# charge_controller.net
KiCad netlist of a schematic drawn in EAGLE
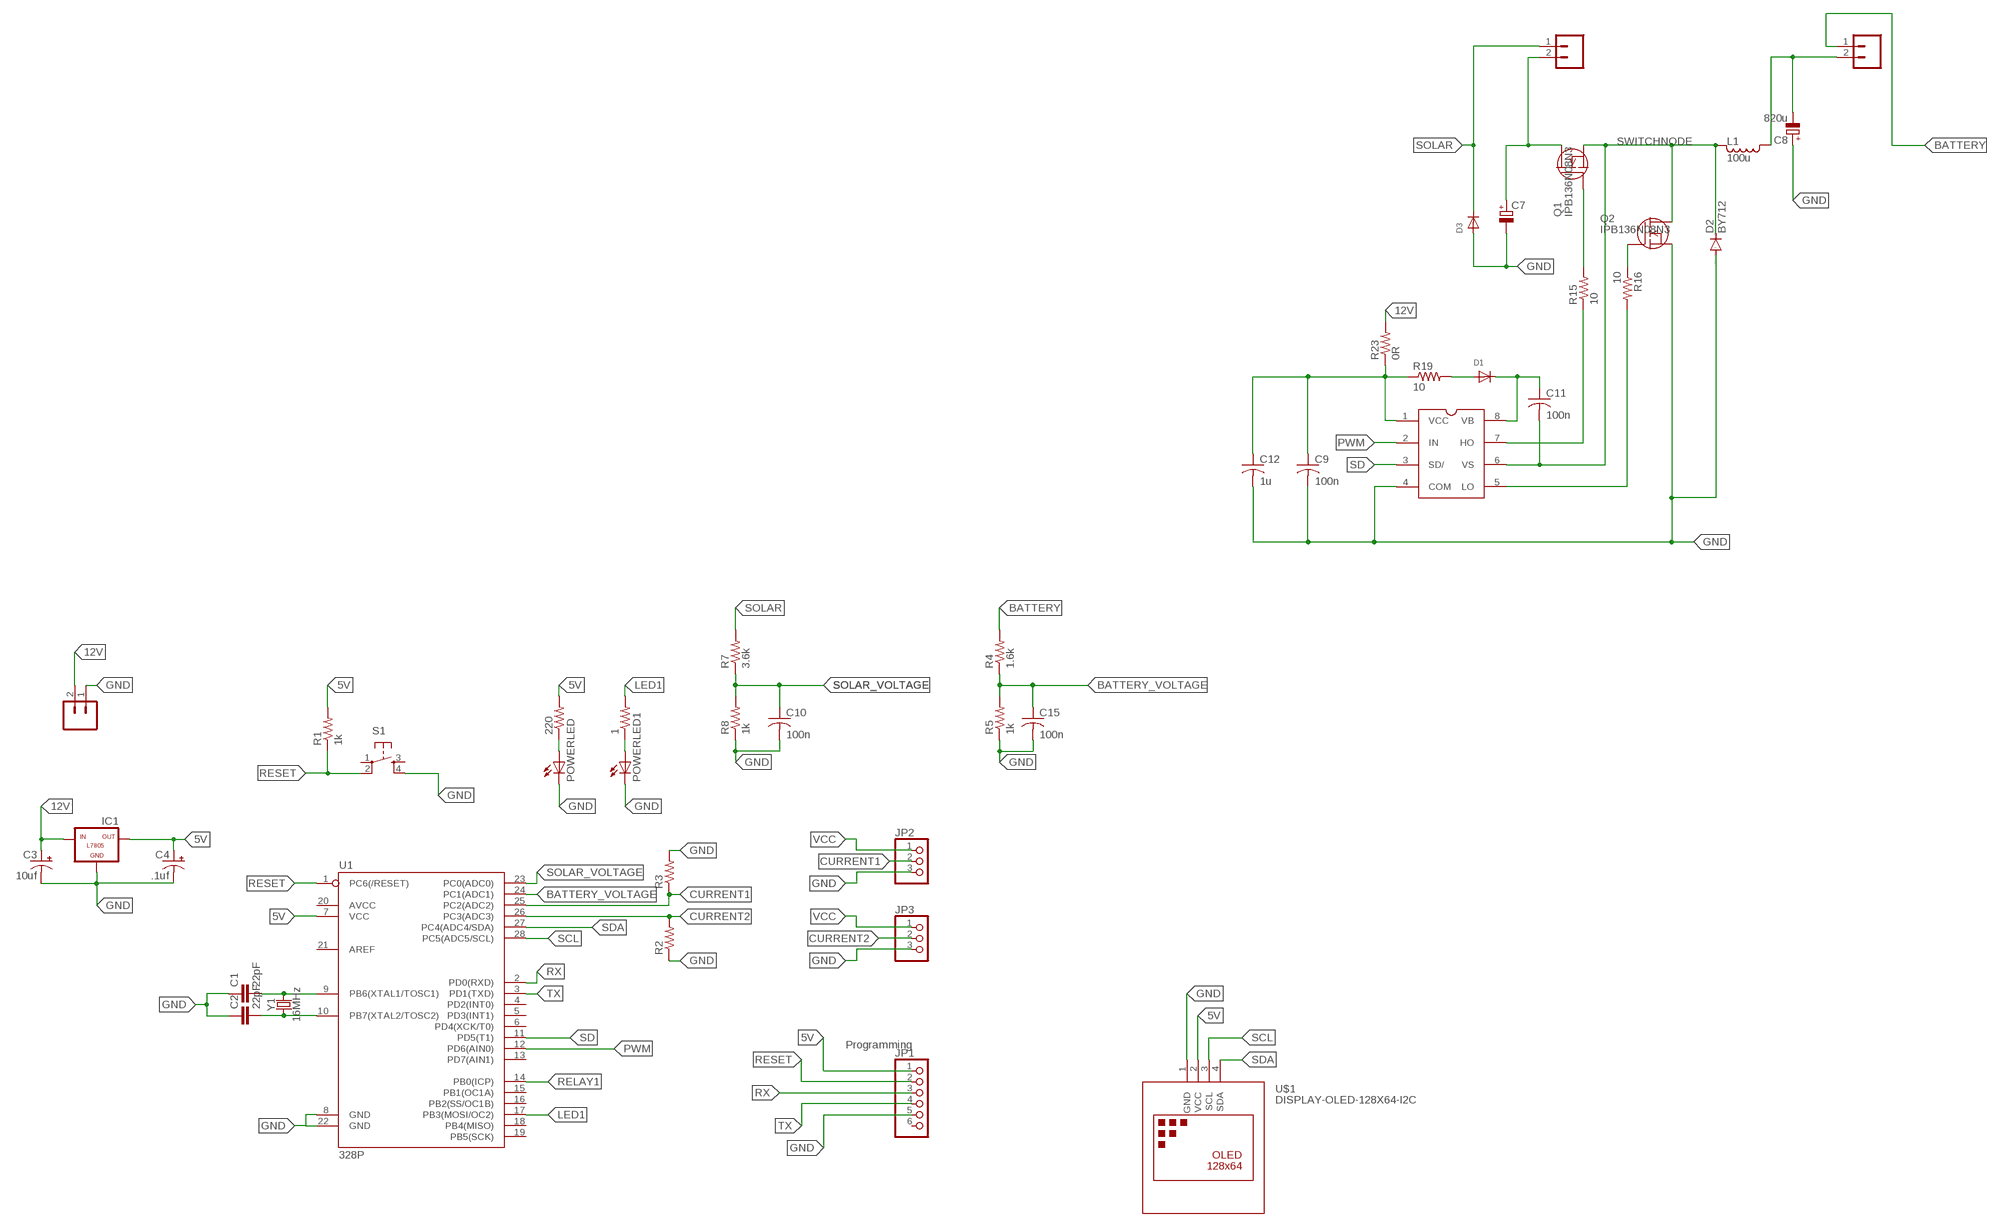
[diagram p0: schematic, sheet 1]

(export (version "E")
  (design (tool "Eeschema 10.0.6"))
  (components
    (comp (ref "1")
      (value "R-US_0204/5")
      (footprint "eagle-import:0204_5")
      (libsource (lib "eagle-import") (part "R-US_0204/5"))
    )
    (comp (ref "220")
      (value "R-US_0204/5")
      (footprint "eagle-import:0204_5")
      (libsource (lib "eagle-import") (part "R-US_0204/5"))
    )
    (comp (ref "BATTERY-OUT")
      (value "CONN_023.5MM_LOCK")
      (footprint "eagle-import:SCREWTERMINAL-3.5MM-2_LOCK")
      (libsource (lib "eagle-import") (part "CONN_023.5MM_LOCK"))
    )
    (comp (ref "C1")
      (value "22pF")
      (footprint "eagle-import:CAP-PTH-2.54")
      (libsource (lib "eagle-import") (part "22PF-PTH-2.54MM-200V-5%"))
    )
    (comp (ref "C2")
      (value "22pF")
      (footprint "eagle-import:CAP-PTH-2.54")
      (libsource (lib "eagle-import") (part "22PF-PTH-2.54MM-200V-5%"))
    )
    (comp (ref "C3")
      (value "10uf")
      (footprint "eagle-import:E5-5")
      (libsource (lib "eagle-import") (part "CPOL-USE5-5"))
    )
    (comp (ref "C4")
      (value ".1uf")
      (footprint "eagle-import:E5-5")
      (libsource (lib "eagle-import") (part "CPOL-USE5-5"))
    )
    (comp (ref "C7")
      (value "680u")
      (footprint "eagle-import:10MM")
      (libsource (lib "eagle-import") (part "C_POLARIZED10MM"))
    )
    (comp (ref "C8")
      (value "820u")
      (footprint "eagle-import:10MM")
      (libsource (lib "eagle-import") (part "C_POLARIZED10MM"))
    )
    (comp (ref "C9")
      (value "100n")
      (footprint "eagle-import:C050-025X075")
      (libsource (lib "eagle-import") (part "C-US050-025X075"))
    )
    (comp (ref "C10")
      (value "100n")
      (footprint "eagle-import:C050-025X075")
      (libsource (lib "eagle-import") (part "C-US050-025X075"))
    )
    (comp (ref "C11")
      (value "100n")
      (footprint "eagle-import:C050-055X075")
      (libsource (lib "eagle-import") (part "C-US050-055X075"))
    )
    (comp (ref "C12")
      (value "1u")
      (footprint "eagle-import:C050-025X075")
      (libsource (lib "eagle-import") (part "C-US050-025X075"))
    )
    (comp (ref "C15")
      (value "100n")
      (footprint "eagle-import:C050-025X075")
      (libsource (lib "eagle-import") (part "C-US050-025X075"))
    )
    (comp (ref "D1")
      (value "DIODEDO-1N4148")
      (footprint "eagle-import:DO-1N4148")
      (libsource (lib "eagle-import") (part "DIODEDO-1N4148"))
    )
    (comp (ref "D2")
      (value "BY712")
      (footprint "eagle-import:SOD61E")
      (libsource (lib "eagle-import") (part "BY712"))
    )
    (comp (ref "D3")
      (value "DIODEDO-1N4148")
      (footprint "eagle-import:DO-1N4148")
      (libsource (lib "eagle-import") (part "DIODEDO-1N4148"))
    )
    (comp (ref "IC1")
      (value "L7805")
      (footprint "eagle-import:78XXL")
      (libsource (lib "eagle-import") (part "L7805"))
    )
    (comp (ref "J1")
      (value "CONN_023.5MM_LOCK")
      (footprint "eagle-import:SCREWTERMINAL-3.5MM-2_LOCK")
      (libsource (lib "eagle-import") (part "CONN_023.5MM_LOCK"))
    )
    (comp (ref "JP1")
      (value "PINHD-1X6")
      (footprint "eagle-import:1X06")
      (libsource (lib "eagle-import") (part "PINHD-1X6"))
    )
    (comp (ref "JP2")
      (value "PINHD-1X3")
      (footprint "eagle-import:1X03")
      (libsource (lib "eagle-import") (part "PINHD-1X3"))
    )
    (comp (ref "JP3")
      (value "PINHD-1X3")
      (footprint "eagle-import:1X03")
      (libsource (lib "eagle-import") (part "PINHD-1X3"))
    )
    (comp (ref "L1")
      (value "100u")
      (footprint "eagle-import:MSS1583")
      (libsource (lib "eagle-import") (part "INDUCTORMSS1583"))
    )
    (comp (ref "POWERLED")
      (value "LED5MM")
      (footprint "eagle-import:LED5MM")
      (libsource (lib "eagle-import") (part "LED5MM"))
    )
    (comp (ref "POWERLED1")
      (value "LED5MM")
      (footprint "eagle-import:LED5MM")
      (libsource (lib "eagle-import") (part "LED5MM"))
    )
    (comp (ref "Q1")
      (value "IPB136N08N3")
      (footprint "eagle-import:TO220")
      (libsource (lib "eagle-import") (part "IRF840"))
    )
    (comp (ref "Q2")
      (value "IPB136N08N3")
      (footprint "eagle-import:TO220")
      (libsource (lib "eagle-import") (part "IRF840"))
    )
    (comp (ref "R1")
      (value "1k")
      (footprint "eagle-import:0204_5")
      (libsource (lib "eagle-import") (part "R-US_0204/5"))
    )
    (comp (ref "R2")
      (value "R-US_0204/5")
      (footprint "eagle-import:0204_5")
      (libsource (lib "eagle-import") (part "R-US_0204/5"))
    )
    (comp (ref "R3")
      (value "R-US_0204/5")
      (footprint "eagle-import:0204_5")
      (libsource (lib "eagle-import") (part "R-US_0204/5"))
    )
    (comp (ref "R4")
      (value "1.6k")
      (footprint "eagle-import:0204_5")
      (libsource (lib "eagle-import") (part "R-US_0204/5"))
    )
    (comp (ref "R5")
      (value "1k")
      (footprint "eagle-import:0204_5")
      (libsource (lib "eagle-import") (part "R-US_0204/5"))
    )
    (comp (ref "R7")
      (value "3.6k")
      (footprint "eagle-import:0204_5")
      (libsource (lib "eagle-import") (part "R-US_0204/5"))
    )
    (comp (ref "R8")
      (value "1k")
      (footprint "eagle-import:0204_5")
      (libsource (lib "eagle-import") (part "R-US_0204/5"))
    )
    (comp (ref "R15")
      (value "10")
      (footprint "eagle-import:0204_7")
      (libsource (lib "eagle-import") (part "R-US_0204/7"))
    )
    (comp (ref "R16")
      (value "10")
      (footprint "eagle-import:0204_7")
      (libsource (lib "eagle-import") (part "R-US_0204/7"))
    )
    (comp (ref "R19")
      (value "10")
      (footprint "eagle-import:0204_7")
      (libsource (lib "eagle-import") (part "R-US_0204/7"))
    )
    (comp (ref "R23")
      (value "0R")
      (footprint "eagle-import:0204_7")
      (libsource (lib "eagle-import") (part "R-US_0204/7"))
    )
    (comp (ref "S1")
      (value "TAC_SWITCHPTH")
      (footprint "eagle-import:TACTILE-PTH")
      (libsource (lib "eagle-import") (part "TAC_SWITCHPTH"))
    )
    (comp (ref "SOLAR-IN")
      (value "CONN_023.5MM_LOCK")
      (footprint "eagle-import:SCREWTERMINAL-3.5MM-2_LOCK")
      (libsource (lib "eagle-import") (part "CONN_023.5MM_LOCK"))
    )
    (comp (ref "U$1")
      (value "DISPLAY-OLED-128X64-I2C")
      (footprint "eagle-import:DISPLAY-OLED-128X64-I2C")
      (libsource (lib "eagle-import") (part "DISPLAY-OLED-128X64-I2C"))
    )
    (comp (ref "U$2")
      (value "IR2104")
      (footprint "eagle-import:IR2104")
      (libsource (lib "eagle-import") (part "IR2104"))
    )
    (comp (ref "U1")
      (value "328P")
      (footprint "eagle-import:DIP28")
      (libsource (lib "eagle-import") (part "ATMEGA328P_PDIP"))
    )
    (comp (ref "Y1")
      (value "16MHz")
      (footprint "eagle-import:HC49US")
      (libsource (lib "eagle-import") (part "CRYSTAL-16MHZPTH-HC49US"))
    )
  )
  (nets
    (net (code "1") (name "/SWITCHNODE") (class "Default")
      (node (ref "C11") (pin "2") (pinfunction "2_2") (pintype "passive"))
      (node (ref "D2") (pin "C") (pinfunction "C_C") (pintype "passive"))
      (node (ref "L1") (pin "2") (pinfunction "2_2") (pintype "passive"))
      (node (ref "Q1") (pin "3") (pinfunction "S_3") (pintype "passive"))
      (node (ref "Q2") (pin "2") (pinfunction "D_2") (pintype "passive"))
      (node (ref "U$2") (pin "6") (pinfunction "VS_6") (pintype "power_in"))
    )
    (net (code "2") (name "5V") (class "Default")
      (node (ref "220") (pin "2") (pinfunction "2_2") (pintype "passive"))
      (node (ref "C4") (pin "+") (pinfunction "+_+") (pintype "passive"))
      (node (ref "IC1") (pin "OUT") (pinfunction "OUT_OUT") (pintype "passive"))
      (node (ref "JP1") (pin "1") (pinfunction "1_1") (pintype "passive"))
      (node (ref "R1") (pin "2") (pinfunction "2_2") (pintype "passive"))
      (node (ref "U$1") (pin "2") (pinfunction "VCC_2") (pintype "power_in"))
      (node (ref "U1") (pin "7") (pinfunction "VCC_7") (pintype "bidirectional"))
    )
    (net (code "3") (name "12V") (class "Default")
      (node (ref "C3") (pin "+") (pinfunction "+_+") (pintype "passive"))
      (node (ref "IC1") (pin "IN") (pinfunction "IN_IN") (pintype "input"))
      (node (ref "J1") (pin "2") (pinfunction "2_2") (pintype "passive"))
      (node (ref "R23") (pin "2") (pinfunction "2_2") (pintype "passive"))
    )
    (net (code "4") (name "BATTERY") (class "Default")
      (node (ref "BATTERY-OUT") (pin "1") (pinfunction "1_1") (pintype "passive"))
      (node (ref "R4") (pin "2") (pinfunction "2_2") (pintype "passive"))
    )
    (net (code "5") (name "BATTERY_VOLTAGE") (class "Default")
      (node (ref "C15") (pin "1") (pinfunction "1_1") (pintype "passive"))
      (node (ref "R4") (pin "1") (pinfunction "1_1") (pintype "passive"))
      (node (ref "R5") (pin "2") (pinfunction "2_2") (pintype "passive"))
      (node (ref "U1") (pin "24") (pinfunction "PC1(ADC1)_24") (pintype "bidirectional"))
    )
    (net (code "6") (name "CURRENT1") (class "Default")
      (node (ref "JP2") (pin "2") (pinfunction "2_2") (pintype "passive"))
      (node (ref "R3") (pin "1") (pinfunction "1_1") (pintype "passive"))
      (node (ref "U1") (pin "25") (pinfunction "PC2(ADC2)_25") (pintype "bidirectional"))
    )
    (net (code "7") (name "CURRENT2") (class "Default")
      (node (ref "JP3") (pin "2") (pinfunction "2_2") (pintype "passive"))
      (node (ref "R2") (pin "2") (pinfunction "2_2") (pintype "passive"))
      (node (ref "U1") (pin "26") (pinfunction "PC3(ADC3)_26") (pintype "bidirectional"))
    )
    (net (code "8") (name "GND") (class "Default")
      (node (ref "C1") (pin "1") (pinfunction "1_1") (pintype "passive"))
      (node (ref "C10") (pin "2") (pinfunction "2_2") (pintype "passive"))
      (node (ref "C12") (pin "2") (pinfunction "2_2") (pintype "passive"))
      (node (ref "C15") (pin "2") (pinfunction "2_2") (pintype "passive"))
      (node (ref "C2") (pin "1") (pinfunction "1_1") (pintype "passive"))
      (node (ref "C3") (pin "-") (pinfunction "-_-") (pintype "passive"))
      (node (ref "C4") (pin "-") (pinfunction "-_-") (pintype "passive"))
      (node (ref "C7") (pin "-") (pinfunction "-_-") (pintype "passive"))
      (node (ref "C8") (pin "+") (pinfunction "+_+") (pintype "passive"))
      (node (ref "C9") (pin "2") (pinfunction "2_2") (pintype "passive"))
      (node (ref "D2") (pin "A") (pinfunction "A_A") (pintype "passive"))
      (node (ref "D3") (pin "A") (pinfunction "A_A") (pintype "passive"))
      (node (ref "IC1") (pin "GND") (pinfunction "GND_GND") (pintype "input"))
      (node (ref "J1") (pin "1") (pinfunction "1_1") (pintype "passive"))
      (node (ref "JP1") (pin "5") (pinfunction "5_5") (pintype "passive"))
      (node (ref "JP2") (pin "3") (pinfunction "3_3") (pintype "passive"))
      (node (ref "JP3") (pin "3") (pinfunction "3_3") (pintype "passive"))
      (node (ref "POWERLED") (pin "K") (pinfunction "C_K") (pintype "passive"))
      (node (ref "POWERLED1") (pin "K") (pinfunction "C_K") (pintype "passive"))
      (node (ref "Q2") (pin "3") (pinfunction "S_3") (pintype "passive"))
      (node (ref "R2") (pin "1") (pinfunction "1_1") (pintype "passive"))
      (node (ref "R3") (pin "2") (pinfunction "2_2") (pintype "passive"))
      (node (ref "R5") (pin "1") (pinfunction "1_1") (pintype "passive"))
      (node (ref "R8") (pin "1") (pinfunction "1_1") (pintype "passive"))
      (node (ref "S1") (pin "4") (pinfunction "4_4") (pintype "passive"))
      (node (ref "U$1") (pin "1") (pinfunction "GND_1") (pintype "power_in"))
      (node (ref "U$2") (pin "4") (pinfunction "COM_4") (pintype "bidirectional"))
      (node (ref "U1") (pin "22") (pinfunction "GND_22") (pintype "bidirectional"))
      (node (ref "U1") (pin "8") (pinfunction "GND_8") (pintype "bidirectional"))
    )
    (net (code "9") (name "LED1") (class "Default")
      (node (ref "1") (pin "2") (pinfunction "2_2") (pintype "passive"))
      (node (ref "U1") (pin "17") (pinfunction "PB3(MOSI/OC2)_17") (pintype "bidirectional"))
    )
    (net (code "10") (name "Net-(1-Pad1)") (class "Default")
      (node (ref "1") (pin "1") (pinfunction "1_1") (pintype "passive"))
      (node (ref "POWERLED1") (pin "A") (pinfunction "A_A") (pintype "passive"))
    )
    (net (code "11") (name "Net-(220-Pad1)") (class "Default")
      (node (ref "220") (pin "1") (pinfunction "1_1") (pintype "passive"))
      (node (ref "POWERLED") (pin "A") (pinfunction "A_A") (pintype "passive"))
    )
    (net (code "12") (name "Net-(BATTERY-OUT-Pad2)") (class "Default")
      (node (ref "BATTERY-OUT") (pin "2") (pinfunction "2_2") (pintype "passive"))
      (node (ref "C8") (pin "-") (pinfunction "-_-") (pintype "passive"))
      (node (ref "L1") (pin "1") (pinfunction "1_1") (pintype "passive"))
    )
    (net (code "13") (name "Net-(D1-PadA)") (class "Default")
      (node (ref "D1") (pin "A") (pinfunction "A_A") (pintype "passive"))
      (node (ref "R19") (pin "2") (pinfunction "2_2") (pintype "passive"))
    )
    (net (code "14") (name "Net-(Q1-D)") (class "Default")
      (node (ref "C7") (pin "+") (pinfunction "+_+") (pintype "passive"))
      (node (ref "Q1") (pin "2") (pinfunction "D_2") (pintype "passive"))
      (node (ref "SOLAR-IN") (pin "2") (pinfunction "2_2") (pintype "passive"))
    )
    (net (code "15") (name "Net-(Q1-G)") (class "Default")
      (node (ref "Q1") (pin "1") (pinfunction "G_1") (pintype "passive"))
      (node (ref "R15") (pin "2") (pinfunction "2_2") (pintype "passive"))
    )
    (net (code "16") (name "Net-(Q2-G)") (class "Default")
      (node (ref "Q2") (pin "1") (pinfunction "G_1") (pintype "passive"))
      (node (ref "R16") (pin "1") (pinfunction "1_1") (pintype "passive"))
    )
    (net (code "17") (name "Net-(U$2-HO)") (class "Default")
      (node (ref "R15") (pin "1") (pinfunction "1_1") (pintype "passive"))
      (node (ref "U$2") (pin "7") (pinfunction "HO_7") (pintype "bidirectional"))
    )
    (net (code "18") (name "Net-(U$2-LO)") (class "Default")
      (node (ref "R16") (pin "2") (pinfunction "2_2") (pintype "passive"))
      (node (ref "U$2") (pin "5") (pinfunction "LO_5") (pintype "bidirectional"))
    )
    (net (code "19") (name "Net-(U$2-VB)") (class "Default")
      (node (ref "C11") (pin "1") (pinfunction "1_1") (pintype "passive"))
      (node (ref "D1") (pin "C") (pinfunction "C_C") (pintype "passive"))
      (node (ref "U$2") (pin "8") (pinfunction "VB_8") (pintype "power_in"))
    )
    (net (code "20") (name "Net-(U$2-VCC)") (class "Default")
      (node (ref "C12") (pin "1") (pinfunction "1_1") (pintype "passive"))
      (node (ref "C9") (pin "1") (pinfunction "1_1") (pintype "passive"))
      (node (ref "R19") (pin "1") (pinfunction "1_1") (pintype "passive"))
      (node (ref "R23") (pin "1") (pinfunction "1_1") (pintype "passive"))
      (node (ref "U$2") (pin "1") (pinfunction "VCC_1") (pintype "power_in"))
    )
    (net (code "21") (name "Net-(U1-PB6(XTAL1{slash}TOSC1))") (class "Default")
      (node (ref "C1") (pin "2") (pinfunction "2_2") (pintype "passive"))
      (node (ref "U1") (pin "9") (pinfunction "PB6(XTAL1/TOSC1)_9") (pintype "bidirectional"))
      (node (ref "Y1") (pin "2") (pinfunction "2_2") (pintype "passive"))
    )
    (net (code "22") (name "Net-(U1-PB7(XTAL2{slash}TOSC2))") (class "Default")
      (node (ref "C2") (pin "2") (pinfunction "2_2") (pintype "passive"))
      (node (ref "U1") (pin "10") (pinfunction "PB7(XTAL2/TOSC2)_10") (pintype "bidirectional"))
      (node (ref "Y1") (pin "1") (pinfunction "1_1") (pintype "passive"))
    )
    (net (code "23") (name "PWM") (class "Default")
      (node (ref "U$2") (pin "2") (pinfunction "IN_2") (pintype "bidirectional"))
      (node (ref "U1") (pin "12") (pinfunction "PD6(AIN0)_12") (pintype "bidirectional"))
    )
    (net (code "24") (name "RELAY1") (class "Default")
      (node (ref "U1") (pin "14") (pinfunction "PB0(ICP)_14") (pintype "bidirectional"))
    )
    (net (code "25") (name "RESET") (class "Default")
      (node (ref "JP1") (pin "2") (pinfunction "2_2") (pintype "passive"))
      (node (ref "R1") (pin "1") (pinfunction "1_1") (pintype "passive"))
      (node (ref "S1") (pin "2") (pinfunction "2_2") (pintype "passive"))
      (node (ref "U1") (pin "1") (pinfunction "PC6(/RESET)_1") (pintype "bidirectional"))
    )
    (net (code "26") (name "RX") (class "Default")
      (node (ref "JP1") (pin "3") (pinfunction "3_3") (pintype "passive"))
      (node (ref "U1") (pin "2") (pinfunction "PD0(RXD)_2") (pintype "bidirectional"))
    )
    (net (code "27") (name "SCL") (class "Default")
      (node (ref "U$1") (pin "3") (pinfunction "SCL_3") (pintype "bidirectional"))
      (node (ref "U1") (pin "28") (pinfunction "PC5(ADC5/SCL)_28") (pintype "bidirectional"))
    )
    (net (code "28") (name "SD") (class "Default")
      (node (ref "U$2") (pin "3") (pinfunction "SD/_3") (pintype "bidirectional"))
      (node (ref "U1") (pin "11") (pinfunction "PD5(T1)_11") (pintype "bidirectional"))
    )
    (net (code "29") (name "SDA") (class "Default")
      (node (ref "U$1") (pin "4") (pinfunction "SDA_4") (pintype "bidirectional"))
      (node (ref "U1") (pin "27") (pinfunction "PC4(ADC4/SDA)_27") (pintype "bidirectional"))
    )
    (net (code "30") (name "SOLAR") (class "Default")
      (node (ref "D3") (pin "C") (pinfunction "C_C") (pintype "passive"))
      (node (ref "R7") (pin "2") (pinfunction "2_2") (pintype "passive"))
      (node (ref "SOLAR-IN") (pin "1") (pinfunction "1_1") (pintype "passive"))
    )
    (net (code "31") (name "SOLAR_VOLTAGE") (class "Default")
      (node (ref "C10") (pin "1") (pinfunction "1_1") (pintype "passive"))
      (node (ref "R7") (pin "1") (pinfunction "1_1") (pintype "passive"))
      (node (ref "R8") (pin "2") (pinfunction "2_2") (pintype "passive"))
      (node (ref "U1") (pin "23") (pinfunction "PC0(ADC0)_23") (pintype "bidirectional"))
    )
    (net (code "32") (name "TX") (class "Default")
      (node (ref "JP1") (pin "4") (pinfunction "4_4") (pintype "passive"))
      (node (ref "U1") (pin "3") (pinfunction "PD1(TXD)_3") (pintype "bidirectional"))
    )
    (net (code "33") (name "VCC") (class "Default")
      (node (ref "JP2") (pin "1") (pinfunction "1_1") (pintype "passive"))
      (node (ref "JP3") (pin "1") (pinfunction "1_1") (pintype "passive"))
    )
    (net (code "34") (name "unconnected-(JP1-Pad6)") (class "Default")
      (node (ref "JP1") (pin "6") (pinfunction "6_6") (pintype "passive"))
    )
    (net (code "35") (name "unconnected-(S1-Pad1)") (class "Default")
      (node (ref "S1") (pin "1") (pinfunction "1_1") (pintype "passive"))
    )
    (net (code "36") (name "unconnected-(S1-Pad3)") (class "Default")
      (node (ref "S1") (pin "3") (pinfunction "3_3") (pintype "passive"))
    )
    (net (code "37") (name "unconnected-(U1-AREF-Pad21)") (class "Default")
      (node (ref "U1") (pin "21") (pinfunction "AREF_21") (pintype "bidirectional"))
    )
    (net (code "38") (name "unconnected-(U1-AVCC-Pad20)") (class "Default")
      (node (ref "U1") (pin "20") (pinfunction "AVCC_20") (pintype "bidirectional"))
    )
    (net (code "39") (name "unconnected-(U1-PB1(OC1A)-Pad15)") (class "Default")
      (node (ref "U1") (pin "15") (pinfunction "PB1(OC1A)_15") (pintype "bidirectional"))
    )
    (net (code "40") (name "unconnected-(U1-PB2(SS{slash}OC1B)-Pad16)") (class "Default")
      (node (ref "U1") (pin "16") (pinfunction "PB2(SS/OC1B)_16") (pintype "bidirectional"))
    )
    (net (code "41") (name "unconnected-(U1-PB4(MISO)-Pad18)") (class "Default")
      (node (ref "U1") (pin "18") (pinfunction "PB4(MISO)_18") (pintype "bidirectional"))
    )
    (net (code "42") (name "unconnected-(U1-PB5(SCK)-Pad19)") (class "Default")
      (node (ref "U1") (pin "19") (pinfunction "PB5(SCK)_19") (pintype "bidirectional"))
    )
    (net (code "43") (name "unconnected-(U1-PD2(INT0)-Pad4)") (class "Default")
      (node (ref "U1") (pin "4") (pinfunction "PD2(INT0)_4") (pintype "bidirectional"))
    )
    (net (code "44") (name "unconnected-(U1-PD3(INT1)-Pad5)") (class "Default")
      (node (ref "U1") (pin "5") (pinfunction "PD3(INT1)_5") (pintype "bidirectional"))
    )
    (net (code "45") (name "unconnected-(U1-PD4(XCK{slash}T0)-Pad6)") (class "Default")
      (node (ref "U1") (pin "6") (pinfunction "PD4(XCK/T0)_6") (pintype "bidirectional"))
    )
    (net (code "46") (name "unconnected-(U1-PD7(AIN1)-Pad13)") (class "Default")
      (node (ref "U1") (pin "13") (pinfunction "PD7(AIN1)_13") (pintype "bidirectional"))
    )
  )
)
